# AUDIO_FM_LC_00.net
KiCad netlist of a schematic drawn in Altium Designer
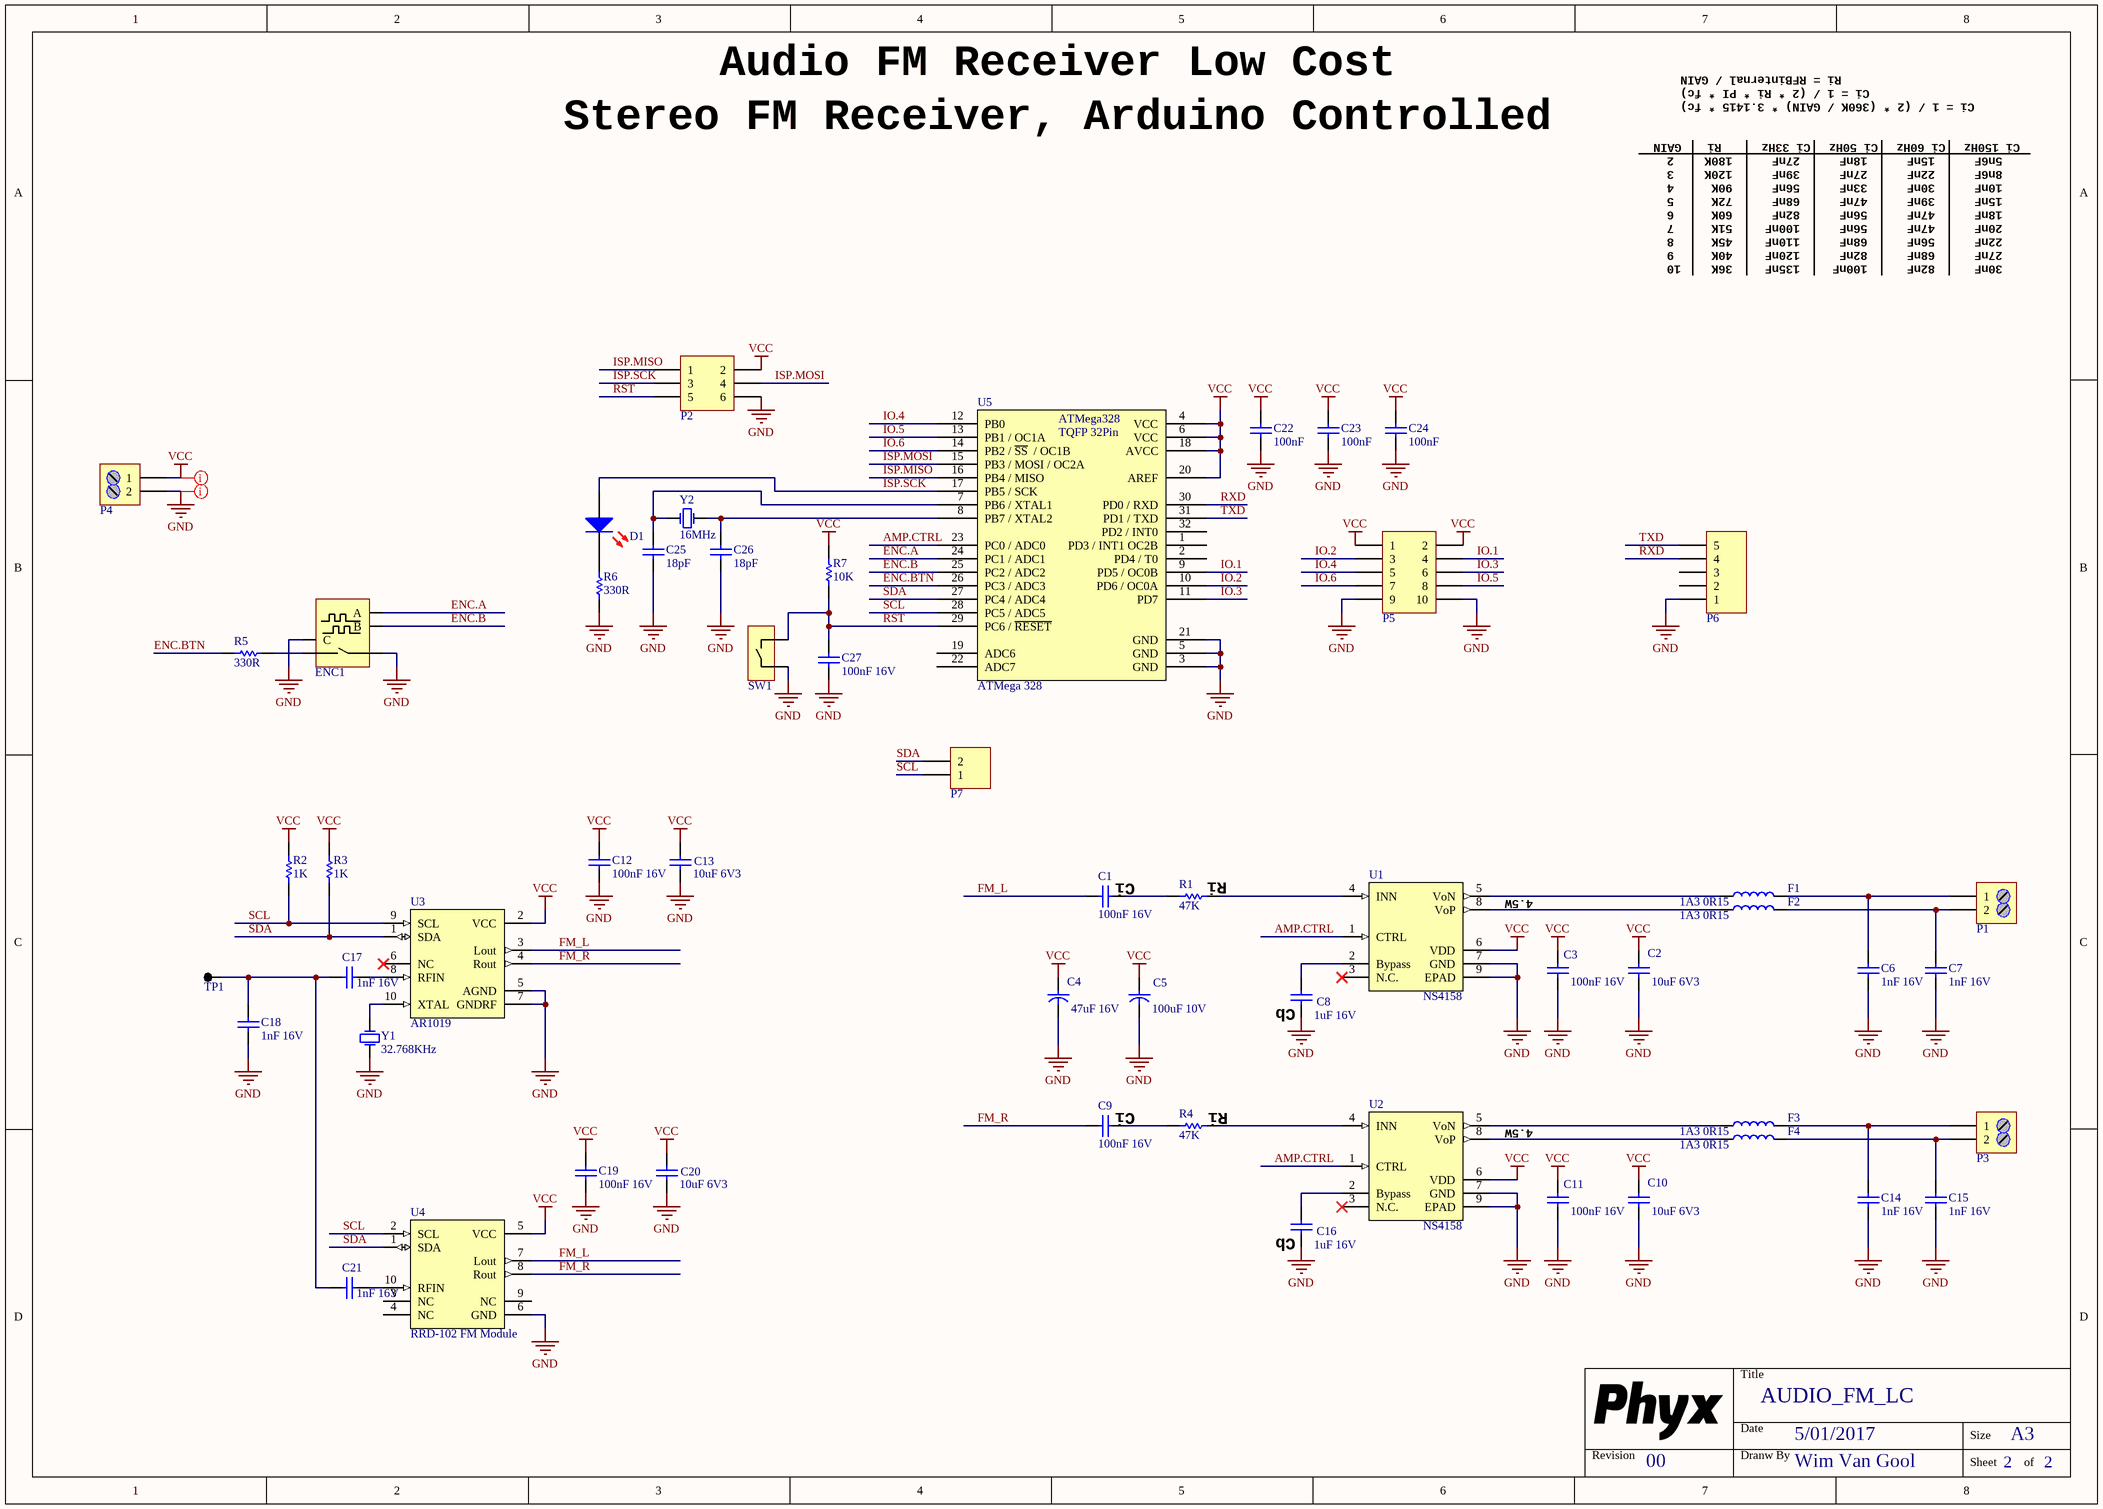
[diagram p0: AUDIO_FM_LC_00.SchDoc]

(export (version "E")
  (design (tool "Eeschema 10.0.6"))
  (components
    (comp (ref "C1")
      (value "100nF 16V")
      (footprint "C0603_N")
      (description "Capacitor Ceramic")
      (fields (field (name "Comment") "CAP_CERAMIC"))
      (libsource (lib "Phyx_Components") (part "CAP_CERAMIC"))
    )
    (comp (ref "C2")
      (value "10uF 6V3")
      (footprint "C0805_N")
      (description "Capacitor Ceramic")
      (fields (field (name "Comment") "CAP_CERAMIC"))
      (libsource (lib "Phyx_Components") (part "CAP_CERAMIC"))
    )
    (comp (ref "C3")
      (value "100nF 16V")
      (footprint "C0603_N")
      (description "Capacitor Ceramic")
      (fields (field (name "Comment") "CAP_CERAMIC"))
      (libsource (lib "Phyx_Components") (part "CAP_CERAMIC"))
    )
    (comp (ref "C4")
      (value "47uF 16V")
      (footprint "C6.6x5.4")
      (description "Capacitor electrolyt")
      (fields (field (name "Comment") "CAP_POL"))
      (libsource (lib "Phyx_Components") (part "CAP_POL"))
    )
    (comp (ref "C5")
      (value "100uF 10V")
      (footprint "C_5x11_2mm")
      (description "Capacitor electrolyt")
      (fields (field (name "Comment") "CAP_POL"))
      (libsource (lib "Phyx_Components") (part "CAP_POL"))
    )
    (comp (ref "C6")
      (value "1nF 16V")
      (footprint "C0603_N")
      (description "Capacitor Ceramic")
      (fields (field (name "Comment") "CAP_CERAMIC"))
      (libsource (lib "Phyx_Components") (part "CAP_CERAMIC"))
    )
    (comp (ref "C7")
      (value "1nF 16V")
      (footprint "C0603_N")
      (description "Capacitor Ceramic")
      (fields (field (name "Comment") "CAP_CERAMIC"))
      (libsource (lib "Phyx_Components") (part "CAP_CERAMIC"))
    )
    (comp (ref "C8")
      (value "1uF 16V")
      (footprint "C0805_N")
      (description "Capacitor Ceramic")
      (fields (field (name "Comment") "CAP_CERAMIC"))
      (libsource (lib "Phyx_Components") (part "CAP_CERAMIC"))
    )
    (comp (ref "C9")
      (value "100nF 16V")
      (footprint "C0603_N")
      (description "Capacitor Ceramic")
      (fields (field (name "Comment") "CAP_CERAMIC"))
      (libsource (lib "Phyx_Components") (part "CAP_CERAMIC"))
    )
    (comp (ref "C10")
      (value "10uF 6V3")
      (footprint "C0805_N")
      (description "Capacitor Ceramic")
      (fields (field (name "Comment") "CAP_CERAMIC"))
      (libsource (lib "Phyx_Components") (part "CAP_CERAMIC"))
    )
    (comp (ref "C11")
      (value "100nF 16V")
      (footprint "C0603_N")
      (description "Capacitor Ceramic")
      (fields (field (name "Comment") "CAP_CERAMIC"))
      (libsource (lib "Phyx_Components") (part "CAP_CERAMIC"))
    )
    (comp (ref "C12")
      (value "100nF 16V")
      (footprint "C0603_N")
      (description "Capacitor Ceramic")
      (fields (field (name "Comment") "CAP_CERAMIC"))
      (libsource (lib "Phyx_Components") (part "CAP_CERAMIC"))
    )
    (comp (ref "C13")
      (value "10uF 6V3")
      (footprint "C0805_N")
      (description "Capacitor Ceramic")
      (fields (field (name "Comment") "CAP_CERAMIC"))
      (libsource (lib "Phyx_Components") (part "CAP_CERAMIC"))
    )
    (comp (ref "C14")
      (value "1nF 16V")
      (footprint "C0603_N")
      (description "Capacitor Ceramic")
      (fields (field (name "Comment") "CAP_CERAMIC"))
      (libsource (lib "Phyx_Components") (part "CAP_CERAMIC"))
    )
    (comp (ref "C15")
      (value "1nF 16V")
      (footprint "C0603_N")
      (description "Capacitor Ceramic")
      (fields (field (name "Comment") "CAP_CERAMIC"))
      (libsource (lib "Phyx_Components") (part "CAP_CERAMIC"))
    )
    (comp (ref "C16")
      (value "1uF 16V")
      (footprint "C0805_N")
      (description "Capacitor Ceramic")
      (fields (field (name "Comment") "CAP_CERAMIC"))
      (libsource (lib "Phyx_Components") (part "CAP_CERAMIC"))
    )
    (comp (ref "C17")
      (value "1nF 16V")
      (footprint "C0603_N")
      (description "Capacitor Ceramic")
      (fields (field (name "Comment") "CAP_CERAMIC"))
      (libsource (lib "Phyx_Components") (part "CAP_CERAMIC"))
    )
    (comp (ref "C18")
      (value "1nF 16V")
      (footprint "C0603_N")
      (description "Capacitor Ceramic")
      (fields (field (name "Comment") "CAP_CERAMIC"))
      (libsource (lib "Phyx_Components") (part "CAP_CERAMIC"))
    )
    (comp (ref "C19")
      (value "100nF 16V")
      (footprint "C0603_N")
      (description "Capacitor Ceramic")
      (fields (field (name "Comment") "CAP_CERAMIC"))
      (libsource (lib "Phyx_Components") (part "CAP_CERAMIC"))
    )
    (comp (ref "C20")
      (value "10uF 6V3")
      (footprint "C0805_N")
      (description "Capacitor Ceramic")
      (fields (field (name "Comment") "CAP_CERAMIC"))
      (libsource (lib "Phyx_Components") (part "CAP_CERAMIC"))
    )
    (comp (ref "C21")
      (value "1nF 16V")
      (footprint "C0603_N")
      (description "Capacitor Ceramic")
      (fields (field (name "Comment") "CAP_CERAMIC"))
      (libsource (lib "Phyx_Components") (part "CAP_CERAMIC"))
    )
    (comp (ref "C22")
      (value "100nF")
      (footprint "C0603_N")
      (description "Capacitor Ceramic")
      (fields (field (name "Comment") "CAP_CERAMIC"))
      (libsource (lib "Phyx_Components") (part "CAP_CERAMIC"))
    )
    (comp (ref "C23")
      (value "100nF")
      (footprint "C0603_N")
      (description "Capacitor Ceramic")
      (fields (field (name "Comment") "CAP_CERAMIC"))
      (libsource (lib "Phyx_Components") (part "CAP_CERAMIC"))
    )
    (comp (ref "C24")
      (value "100nF")
      (footprint "C0603_N")
      (description "Capacitor Ceramic")
      (fields (field (name "Comment") "CAP_CERAMIC"))
      (libsource (lib "Phyx_Components") (part "CAP_CERAMIC"))
    )
    (comp (ref "C25")
      (value "18pF")
      (footprint "C0603_N")
      (description "Capacitor Ceramic")
      (fields (field (name "Comment") "CAP_CERAMIC"))
      (libsource (lib "Phyx_Components") (part "CAP_CERAMIC"))
    )
    (comp (ref "C26")
      (value "18pF")
      (footprint "C0603_N")
      (description "Capacitor Ceramic")
      (fields (field (name "Comment") "CAP_CERAMIC"))
      (libsource (lib "Phyx_Components") (part "CAP_CERAMIC"))
    )
    (comp (ref "C27")
      (value "100nF 16V")
      (footprint "C0603_N")
      (description "Capacitor Ceramic")
      (fields (field (name "Comment") "CAP_CERAMIC"))
      (libsource (lib "Phyx_Components") (part "CAP_CERAMIC"))
    )
    (comp (ref "D1")
      (value "Default 0805 Red LED")
      (footprint "LED_0805_RD")
      (description "=Description")
      (libsource (lib "Phyx_Components") (part "LED_RED"))
    )
    (comp (ref "ENC1")
      (value "Rotary Encoder with Switch")
      (footprint "PEC11-4215F-S0024")
      (libsource (lib "Phyx_Components") (part "ROT_ENC_3P_SW"))
    )
    (comp (ref "F1")
      (value "1A3 0R15")
      (footprint "L0603")
      (fields (field (name "Comment") "BLM18KG601SN1D"))
      (libsource (lib "Phyx_Components") (part "FERRITE"))
    )
    (comp (ref "F2")
      (value "1A3 0R15")
      (footprint "L0603")
      (fields (field (name "Comment") "BLM18KG601SN1D"))
      (libsource (lib "Phyx_Components") (part "FERRITE"))
    )
    (comp (ref "F3")
      (value "1A3 0R15")
      (footprint "L0603")
      (fields (field (name "Comment") "BLM18KG601SN1D"))
      (libsource (lib "Phyx_Components") (part "FERRITE"))
    )
    (comp (ref "F4")
      (value "1A3 0R15")
      (footprint "L0603")
      (fields (field (name "Comment") "BLM18KG601SN1D"))
      (libsource (lib "Phyx_Components") (part "FERRITE"))
    )
    (comp (ref "P1")
      (value "2 Way Screw HDR 3,5mm")
      (footprint "WE_691103110002")
      (libsource (lib "Phyx_Components") (part "TERM_BLCK_2"))
    )
    (comp (ref "P2")
      (value "Header 3X2")
      (footprint "HDR2X3")
      (libsource (lib "Phyx_Components") (part "Header 3X2"))
    )
    (comp (ref "P3")
      (value "2 Way Screw HDR 3,5mm")
      (footprint "WE_691103110002")
      (libsource (lib "Phyx_Components") (part "TERM_BLCK_2"))
    )
    (comp (ref "P4")
      (value "2 Way Screw HDR 3,5mm")
      (footprint "WE_691103110002")
      (libsource (lib "") (part "TERM_BLCK_2_1"))
    )
    (comp (ref "P5")
      (value "Header 5x2")
      (footprint "HDR2X5")
      (libsource (lib "Phyx_Components") (part "Header 5X2"))
    )
    (comp (ref "P6")
      (value "Header 5")
      (footprint "HDR1X5")
      (libsource (lib "Phyx_Components") (part "Header 5"))
    )
    (comp (ref "P7")
      (value "Header 2")
      (footprint "HDR1X2")
      (description "Pin Header 2.54mm 2way")
      (libsource (lib "Phyx_Components") (part "Header 2"))
    )
    (comp (ref "R1")
      (value "47K")
      (footprint "R0603_N")
      (fields (field (name "Comment") "RESISTOR"))
      (libsource (lib "Phyx_Components") (part "RESISTOR"))
    )
    (comp (ref "R2")
      (value "1K")
      (footprint "R0603_N")
      (fields (field (name "Comment") "RESISTOR"))
      (libsource (lib "Phyx_Components") (part "RESISTOR"))
    )
    (comp (ref "R3")
      (value "1K")
      (footprint "R0603_N")
      (fields (field (name "Comment") "RESISTOR"))
      (libsource (lib "Phyx_Components") (part "RESISTOR"))
    )
    (comp (ref "R4")
      (value "47K")
      (footprint "R0603_N")
      (fields (field (name "Comment") "RESISTOR"))
      (libsource (lib "Phyx_Components") (part "RESISTOR"))
    )
    (comp (ref "R5")
      (value "330R")
      (footprint "R0603_N")
      (fields (field (name "Comment") "RESISTOR"))
      (libsource (lib "Phyx_Components") (part "RESISTOR"))
    )
    (comp (ref "R6")
      (value "330R")
      (footprint "R0603_N")
      (fields (field (name "Comment") "RESISTOR"))
      (libsource (lib "Phyx_Components") (part "RESISTOR"))
    )
    (comp (ref "R7")
      (value "10K")
      (footprint "R0603_N")
      (fields (field (name "Comment") "RESISTOR"))
      (libsource (lib "Phyx_Components") (part "RESISTOR"))
    )
    (comp (ref "SW1")
      (value "Default TH TACT")
      (footprint "TACTSW")
      (description "SW TACT")
      (libsource (lib "Phyx_Components") (part "SW_TACT"))
    )
    (comp (ref "TP1")
      (value "TEST_PAD")
      (footprint "TP_1.5mm_0.9mm")
      (libsource (lib "Phyx_Components") (part "TEST_PAD"))
    )
    (comp (ref "U1")
      (value "NS4158")
      (footprint "SOIC_N_8_TH")
      (description "=Description")
      (fields (field (name "Comment") "5W Class D mono amplifier inducter-less"))
      (libsource (lib "Phyx_Components") (part "NS4158"))
    )
    (comp (ref "U2")
      (value "NS4158")
      (footprint "SOIC_N_8_TH")
      (description "=Description")
      (fields (field (name "Comment") "5W Class D mono amplifier inducter-less"))
      (libsource (lib "Phyx_Components") (part "NS4158"))
    )
    (comp (ref "U3")
      (value "AR1019")
      (footprint "TI_DGS_S-PDSO-G10")
      (description "=Description")
      (fields (field (name "Comment") "FM Receiver I2C"))
      (libsource (lib "Phyx_Components") (part "AR1019"))
    )
    (comp (ref "U4")
      (value "RRD-102 FM Module")
      (footprint "RRD-102")
      (description "=Description")
      (fields (field (name "Comment") "RRD-102 V2.0 FM Radio Module With RDS decoding"))
      (libsource (lib "Phyx_Components") (part "RRD-102"))
    )
    (comp (ref "U5")
      (value "ATMega 328")
      (footprint "TQFP_32")
      (description "ATMega328 SMD TQFP")
      (fields (field (name "Comment") "8-bit MCU"))
      (libsource (lib "Phyx_Components") (part "ATMega328_TQFP32"))
    )
    (comp (ref "Y1")
      (value "32.768KHz")
      (footprint "CMR200T")
      (description "Crystal Oscillator")
      (fields (field (name "Comment") "32.768Khz CMR200 12.5pF"))
      (libsource (lib "Phyx_Components") (part "XTAL"))
    )
    (comp (ref "Y2")
      (value "16MHz")
      (footprint "HC49US")
      (description "Crystal Oscillator")
      (fields (field (name "Comment") "16MHz 18pF HC49US"))
      (libsource (lib "Phyx_Components") (part "XTAL"))
    )
  )
  (nets
    (net (code "1") (name "/AMP.CTRL") (class "Default")
      (node (ref "U1") (pin "1") (pinfunction "CTRL_1") (pintype "input"))
      (node (ref "U2") (pin "1") (pinfunction "CTRL_1") (pintype "input"))
      (node (ref "U5") (pin "23") (pinfunction "PC0_/_ADC0_23") (pintype "passive"))
    )
    (net (code "2") (name "/ENC.A") (class "Default")
      (node (ref "ENC1") (pin "A") (pinfunction "A_A") (pintype "passive"))
      (node (ref "U5") (pin "24") (pinfunction "PC1_/_ADC1_24") (pintype "passive"))
    )
    (net (code "3") (name "/ENC.B") (class "Default")
      (node (ref "ENC1") (pin "B") (pinfunction "B_B") (pintype "passive"))
      (node (ref "U5") (pin "25") (pinfunction "PC2_/_ADC2_25") (pintype "passive"))
    )
    (net (code "4") (name "/ENC.BTN") (class "Default")
      (node (ref "R5") (pin "1") (pinfunction "1_1") (pintype "passive"))
      (node (ref "U5") (pin "26") (pinfunction "PC3_/_ADC3_26") (pintype "passive"))
    )
    (net (code "5") (name "/FM_L") (class "Default")
      (node (ref "C1") (pin "1") (pinfunction "1_1") (pintype "passive"))
      (node (ref "U3") (pin "3") (pinfunction "Lout_3") (pintype "output"))
      (node (ref "U4") (pin "7") (pinfunction "Lout_7") (pintype "output"))
    )
    (net (code "6") (name "/FM_R") (class "Default")
      (node (ref "C9") (pin "1") (pinfunction "1_1") (pintype "passive"))
      (node (ref "U3") (pin "4") (pinfunction "Rout_4") (pintype "output"))
      (node (ref "U4") (pin "8") (pinfunction "Rout_8") (pintype "output"))
    )
    (net (code "7") (name "/IO.1") (class "Default")
      (node (ref "P5") (pin "4") (pinfunction "4_4") (pintype "passive"))
      (node (ref "U5") (pin "9") (pinfunction "PD5_/_OC0B_9") (pintype "passive"))
    )
    (net (code "8") (name "/IO.2") (class "Default")
      (node (ref "P5") (pin "3") (pinfunction "3_3") (pintype "passive"))
      (node (ref "U5") (pin "10") (pinfunction "PD6_/_OC0A_10") (pintype "passive"))
    )
    (net (code "9") (name "/IO.3") (class "Default")
      (node (ref "P5") (pin "6") (pinfunction "6_6") (pintype "passive"))
      (node (ref "U5") (pin "11") (pinfunction "PD7_11") (pintype "passive"))
    )
    (net (code "10") (name "/IO.4") (class "Default")
      (node (ref "P5") (pin "5") (pinfunction "5_5") (pintype "passive"))
      (node (ref "U5") (pin "12") (pinfunction "PB0_12") (pintype "passive"))
    )
    (net (code "11") (name "/IO.5") (class "Default")
      (node (ref "P5") (pin "8") (pinfunction "8_8") (pintype "passive"))
      (node (ref "U5") (pin "13") (pinfunction "PB1_/_OC1A_13") (pintype "passive"))
    )
    (net (code "12") (name "/IO.6") (class "Default")
      (node (ref "P5") (pin "7") (pinfunction "7_7") (pintype "passive"))
      (node (ref "U5") (pin "14") (pinfunction "PB2_/_~{SS}__/_OC1B_14") (pintype "passive"))
    )
    (net (code "13") (name "/ISP.MISO") (class "Default")
      (node (ref "P2") (pin "1") (pinfunction "1_1") (pintype "passive"))
      (node (ref "U5") (pin "16") (pinfunction "PB4_/_MISO_16") (pintype "passive"))
    )
    (net (code "14") (name "/ISP.MOSI") (class "Default")
      (node (ref "P2") (pin "4") (pinfunction "4_4") (pintype "passive"))
      (node (ref "U5") (pin "15") (pinfunction "PB3_/_MOSI_/_OC2A_15") (pintype "passive"))
    )
    (net (code "15") (name "/ISP.SCK") (class "Default")
      (node (ref "D1") (pin "1") (pinfunction "A_1") (pintype "passive"))
      (node (ref "P2") (pin "3") (pinfunction "3_3") (pintype "passive"))
      (node (ref "U5") (pin "17") (pinfunction "PB5_/_SCK_17") (pintype "passive"))
    )
    (net (code "16") (name "/RST") (class "Default")
      (node (ref "C27") (pin "1") (pinfunction "1_1") (pintype "passive"))
      (node (ref "P2") (pin "5") (pinfunction "5_5") (pintype "passive"))
      (node (ref "R7") (pin "2") (pinfunction "2_2") (pintype "passive"))
      (node (ref "SW1") (pin "1") (pinfunction "1_1") (pintype "passive"))
      (node (ref "U5") (pin "29") (pinfunction "PC6_/_~{RESET}_29") (pintype "passive"))
    )
    (net (code "17") (name "/RXD") (class "Default")
      (node (ref "P6") (pin "4") (pinfunction "4_4") (pintype "passive"))
      (node (ref "U5") (pin "30") (pinfunction "PD0_/_RXD_30") (pintype "passive"))
    )
    (net (code "18") (name "/SCL") (class "Default")
      (node (ref "P7") (pin "1") (pinfunction "1_1") (pintype "passive"))
      (node (ref "R2") (pin "2") (pinfunction "2_2") (pintype "passive"))
      (node (ref "U3") (pin "9") (pinfunction "SCL_9") (pintype "input"))
      (node (ref "U4") (pin "2") (pinfunction "SCL_2") (pintype "input"))
      (node (ref "U5") (pin "28") (pinfunction "PC5_/_ADC5_28") (pintype "passive"))
    )
    (net (code "19") (name "/SDA") (class "Default")
      (node (ref "P7") (pin "2") (pinfunction "2_2") (pintype "passive"))
      (node (ref "R3") (pin "2") (pinfunction "2_2") (pintype "passive"))
      (node (ref "U3") (pin "1") (pinfunction "SDA_1") (pintype "bidirectional"))
      (node (ref "U4") (pin "1") (pinfunction "SDA_1") (pintype "bidirectional"))
      (node (ref "U5") (pin "27") (pinfunction "PC4_/_ADC4_27") (pintype "passive"))
    )
    (net (code "20") (name "/TXD") (class "Default")
      (node (ref "P6") (pin "5") (pinfunction "5_5") (pintype "passive"))
      (node (ref "U5") (pin "31") (pinfunction "PD1_/_TXD_31") (pintype "passive"))
    )
    (net (code "21") (name "GND") (class "Default")
      (node (ref "C10") (pin "2") (pinfunction "2_2") (pintype "passive"))
      (node (ref "C11") (pin "2") (pinfunction "2_2") (pintype "passive"))
      (node (ref "C12") (pin "2") (pinfunction "2_2") (pintype "passive"))
      (node (ref "C13") (pin "2") (pinfunction "2_2") (pintype "passive"))
      (node (ref "C14") (pin "2") (pinfunction "2_2") (pintype "passive"))
      (node (ref "C15") (pin "2") (pinfunction "2_2") (pintype "passive"))
      (node (ref "C16") (pin "2") (pinfunction "2_2") (pintype "passive"))
      (node (ref "C18") (pin "2") (pinfunction "2_2") (pintype "passive"))
      (node (ref "C19") (pin "2") (pinfunction "2_2") (pintype "passive"))
      (node (ref "C2") (pin "2") (pinfunction "2_2") (pintype "passive"))
      (node (ref "C20") (pin "2") (pinfunction "2_2") (pintype "passive"))
      (node (ref "C22") (pin "2") (pinfunction "2_2") (pintype "passive"))
      (node (ref "C23") (pin "2") (pinfunction "2_2") (pintype "passive"))
      (node (ref "C24") (pin "2") (pinfunction "2_2") (pintype "passive"))
      (node (ref "C25") (pin "2") (pinfunction "2_2") (pintype "passive"))
      (node (ref "C26") (pin "2") (pinfunction "2_2") (pintype "passive"))
      (node (ref "C27") (pin "2") (pinfunction "2_2") (pintype "passive"))
      (node (ref "C3") (pin "2") (pinfunction "2_2") (pintype "passive"))
      (node (ref "C4") (pin "2") (pinfunction "2_2") (pintype "passive"))
      (node (ref "C5") (pin "2") (pinfunction "2_2") (pintype "passive"))
      (node (ref "C6") (pin "2") (pinfunction "2_2") (pintype "passive"))
      (node (ref "C7") (pin "2") (pinfunction "2_2") (pintype "passive"))
      (node (ref "C8") (pin "2") (pinfunction "2_2") (pintype "passive"))
      (node (ref "ENC1") (pin "2") (pinfunction "2_2") (pintype "passive"))
      (node (ref "ENC1") (pin "C") (pinfunction "C_C") (pintype "passive"))
      (node (ref "P2") (pin "6") (pinfunction "6_6") (pintype "passive"))
      (node (ref "P4") (pin "2") (pinfunction "2_2") (pintype "passive"))
      (node (ref "P5") (pin "10") (pinfunction "10_10") (pintype "passive"))
      (node (ref "P5") (pin "9") (pinfunction "9_9") (pintype "passive"))
      (node (ref "P6") (pin "1") (pinfunction "1_1") (pintype "passive"))
      (node (ref "R6") (pin "2") (pinfunction "2_2") (pintype "passive"))
      (node (ref "SW1") (pin "2") (pinfunction "2_2") (pintype "passive"))
      (node (ref "U1") (pin "7") (pinfunction "GND_7") (pintype "power_in"))
      (node (ref "U1") (pin "9") (pinfunction "EPAD_9") (pintype "power_in"))
      (node (ref "U2") (pin "7") (pinfunction "GND_7") (pintype "power_in"))
      (node (ref "U2") (pin "9") (pinfunction "EPAD_9") (pintype "power_in"))
      (node (ref "U3") (pin "5") (pinfunction "AGND_5") (pintype "power_in"))
      (node (ref "U3") (pin "7") (pinfunction "GNDRF_7") (pintype "power_in"))
      (node (ref "U4") (pin "6") (pinfunction "GND_6") (pintype "power_in"))
      (node (ref "U5") (pin "21") (pinfunction "GND_21") (pintype "passive"))
      (node (ref "U5") (pin "3") (pinfunction "GND_3") (pintype "passive"))
      (node (ref "U5") (pin "5") (pinfunction "GND_5") (pintype "passive"))
      (node (ref "Y1") (pin "2") (pinfunction "OSC2_2") (pintype "passive"))
    )
    (net (code "22") (name "Net-(C1-Pad2)") (class "Default")
      (node (ref "C1") (pin "2") (pinfunction "2_2") (pintype "passive"))
      (node (ref "R1") (pin "2") (pinfunction "2_2") (pintype "passive"))
    )
    (net (code "23") (name "Net-(C6-Pad1)") (class "Default")
      (node (ref "C6") (pin "1") (pinfunction "1_1") (pintype "passive"))
      (node (ref "F1") (pin "2") (pinfunction "2_2") (pintype "passive"))
      (node (ref "P1") (pin "1") (pinfunction "1_1") (pintype "passive"))
    )
    (net (code "24") (name "Net-(C7-Pad1)") (class "Default")
      (node (ref "C7") (pin "1") (pinfunction "1_1") (pintype "passive"))
      (node (ref "F2") (pin "2") (pinfunction "2_2") (pintype "passive"))
      (node (ref "P1") (pin "2") (pinfunction "2_2") (pintype "passive"))
    )
    (net (code "25") (name "Net-(C9-Pad2)") (class "Default")
      (node (ref "C9") (pin "2") (pinfunction "2_2") (pintype "passive"))
      (node (ref "R4") (pin "2") (pinfunction "2_2") (pintype "passive"))
    )
    (net (code "26") (name "Net-(C14-Pad1)") (class "Default")
      (node (ref "C14") (pin "1") (pinfunction "1_1") (pintype "passive"))
      (node (ref "F3") (pin "2") (pinfunction "2_2") (pintype "passive"))
      (node (ref "P3") (pin "1") (pinfunction "1_1") (pintype "passive"))
    )
    (net (code "27") (name "Net-(C15-Pad1)") (class "Default")
      (node (ref "C15") (pin "1") (pinfunction "1_1") (pintype "passive"))
      (node (ref "F4") (pin "2") (pinfunction "2_2") (pintype "passive"))
      (node (ref "P3") (pin "2") (pinfunction "2_2") (pintype "passive"))
    )
    (net (code "28") (name "Net-(C17-Pad2)") (class "Default")
      (node (ref "C17") (pin "2") (pinfunction "2_2") (pintype "passive"))
      (node (ref "C18") (pin "1") (pinfunction "1_1") (pintype "passive"))
      (node (ref "C21") (pin "2") (pinfunction "2_2") (pintype "passive"))
      (node (ref "TP1") (pin "1") (pinfunction "1_1") (pintype "passive"))
    )
    (net (code "29") (name "Net-(D1-K)") (class "Default")
      (node (ref "D1") (pin "2") (pinfunction "K_2") (pintype "passive"))
      (node (ref "R6") (pin "1") (pinfunction "1_1") (pintype "passive"))
    )
    (net (code "30") (name "Net-(ENC1-Pad1)") (class "Default")
      (node (ref "ENC1") (pin "1") (pinfunction "1_1") (pintype "passive"))
      (node (ref "R5") (pin "2") (pinfunction "2_2") (pintype "passive"))
    )
    (net (code "31") (name "Net-(U1-Bypass)") (class "Default")
      (node (ref "C8") (pin "1") (pinfunction "1_1") (pintype "passive"))
      (node (ref "U1") (pin "2") (pinfunction "Bypass_2") (pintype "passive"))
    )
    (net (code "32") (name "Net-(U1-INN)") (class "Default")
      (node (ref "R1") (pin "1") (pinfunction "1_1") (pintype "passive"))
      (node (ref "U1") (pin "4") (pinfunction "INN_4") (pintype "input"))
    )
    (net (code "33") (name "Net-(U1-VoN)") (class "Default")
      (node (ref "F1") (pin "1") (pinfunction "1_1") (pintype "passive"))
      (node (ref "U1") (pin "5") (pinfunction "VoN_5") (pintype "output"))
    )
    (net (code "34") (name "Net-(U1-VoP)") (class "Default")
      (node (ref "F2") (pin "1") (pinfunction "1_1") (pintype "passive"))
      (node (ref "U1") (pin "8") (pinfunction "VoP_8") (pintype "output"))
    )
    (net (code "35") (name "Net-(U2-Bypass)") (class "Default")
      (node (ref "C16") (pin "1") (pinfunction "1_1") (pintype "passive"))
      (node (ref "U2") (pin "2") (pinfunction "Bypass_2") (pintype "passive"))
    )
    (net (code "36") (name "Net-(U2-INN)") (class "Default")
      (node (ref "R4") (pin "1") (pinfunction "1_1") (pintype "passive"))
      (node (ref "U2") (pin "4") (pinfunction "INN_4") (pintype "input"))
    )
    (net (code "37") (name "Net-(U2-VoN)") (class "Default")
      (node (ref "F3") (pin "1") (pinfunction "1_1") (pintype "passive"))
      (node (ref "U2") (pin "5") (pinfunction "VoN_5") (pintype "output"))
    )
    (net (code "38") (name "Net-(U2-VoP)") (class "Default")
      (node (ref "F4") (pin "1") (pinfunction "1_1") (pintype "passive"))
      (node (ref "U2") (pin "8") (pinfunction "VoP_8") (pintype "output"))
    )
    (net (code "39") (name "Net-(U3-RFIN)") (class "Default")
      (node (ref "C17") (pin "1") (pinfunction "1_1") (pintype "passive"))
      (node (ref "U3") (pin "8") (pinfunction "RFIN_8") (pintype "input"))
    )
    (net (code "40") (name "Net-(U3-XTAL)") (class "Default")
      (node (ref "U3") (pin "10") (pinfunction "XTAL_10") (pintype "input"))
      (node (ref "Y1") (pin "1") (pinfunction "OSC1_1") (pintype "passive"))
    )
    (net (code "41") (name "Net-(U4-RFIN)") (class "Default")
      (node (ref "C21") (pin "1") (pinfunction "1_1") (pintype "passive"))
      (node (ref "U4") (pin "10") (pinfunction "RFIN_10") (pintype "input"))
    )
    (net (code "42") (name "Net-(U5-PB6_{slash}_XTAL1)") (class "Default")
      (node (ref "C25") (pin "1") (pinfunction "1_1") (pintype "passive"))
      (node (ref "U5") (pin "7") (pinfunction "PB6_/_XTAL1_7") (pintype "passive"))
      (node (ref "Y2") (pin "1") (pinfunction "OSC1_1") (pintype "passive"))
    )
    (net (code "43") (name "Net-(U5-PB7_{slash}_XTAL2)") (class "Default")
      (node (ref "C26") (pin "1") (pinfunction "1_1") (pintype "passive"))
      (node (ref "U5") (pin "8") (pinfunction "PB7_/_XTAL2_8") (pintype "passive"))
      (node (ref "Y2") (pin "2") (pinfunction "OSC2_2") (pintype "passive"))
    )
    (net (code "44") (name "VCC") (class "Default")
      (node (ref "C10") (pin "1") (pinfunction "1_1") (pintype "passive"))
      (node (ref "C11") (pin "1") (pinfunction "1_1") (pintype "passive"))
      (node (ref "C12") (pin "1") (pinfunction "1_1") (pintype "passive"))
      (node (ref "C13") (pin "1") (pinfunction "1_1") (pintype "passive"))
      (node (ref "C19") (pin "1") (pinfunction "1_1") (pintype "passive"))
      (node (ref "C2") (pin "1") (pinfunction "1_1") (pintype "passive"))
      (node (ref "C20") (pin "1") (pinfunction "1_1") (pintype "passive"))
      (node (ref "C22") (pin "1") (pinfunction "1_1") (pintype "passive"))
      (node (ref "C23") (pin "1") (pinfunction "1_1") (pintype "passive"))
      (node (ref "C24") (pin "1") (pinfunction "1_1") (pintype "passive"))
      (node (ref "C3") (pin "1") (pinfunction "1_1") (pintype "passive"))
      (node (ref "C4") (pin "1") (pinfunction "1_1") (pintype "passive"))
      (node (ref "C5") (pin "1") (pinfunction "1_1") (pintype "passive"))
      (node (ref "P2") (pin "2") (pinfunction "2_2") (pintype "passive"))
      (node (ref "P4") (pin "1") (pinfunction "1_1") (pintype "passive"))
      (node (ref "P5") (pin "1") (pinfunction "1_1") (pintype "passive"))
      (node (ref "P5") (pin "2") (pinfunction "2_2") (pintype "passive"))
      (node (ref "R2") (pin "1") (pinfunction "1_1") (pintype "passive"))
      (node (ref "R3") (pin "1") (pinfunction "1_1") (pintype "passive"))
      (node (ref "R7") (pin "1") (pinfunction "1_1") (pintype "passive"))
      (node (ref "U1") (pin "6") (pinfunction "VDD_6") (pintype "power_in"))
      (node (ref "U2") (pin "6") (pinfunction "VDD_6") (pintype "power_in"))
      (node (ref "U3") (pin "2") (pinfunction "VCC_2") (pintype "power_in"))
      (node (ref "U4") (pin "5") (pinfunction "VCC_5") (pintype "power_in"))
      (node (ref "U5") (pin "18") (pinfunction "AVCC_18") (pintype "passive"))
      (node (ref "U5") (pin "20") (pinfunction "AREF_20") (pintype "passive"))
      (node (ref "U5") (pin "4") (pinfunction "VCC_4") (pintype "passive"))
      (node (ref "U5") (pin "6") (pinfunction "VCC_6") (pintype "passive"))
    )
    (net (code "45") (name "unconnected-(P6-Pad2)") (class "Default")
      (node (ref "P6") (pin "2") (pinfunction "2_2") (pintype "passive"))
    )
    (net (code "46") (name "unconnected-(P6-Pad3)") (class "Default")
      (node (ref "P6") (pin "3") (pinfunction "3_3") (pintype "passive"))
    )
    (net (code "47") (name "unconnected-(U1-N.C.-Pad3)") (class "Default")
      (node (ref "U1") (pin "3") (pinfunction "N.C._3") (pintype "passive+no_connect"))
    )
    (net (code "48") (name "unconnected-(U2-N.C.-Pad3)") (class "Default")
      (node (ref "U2") (pin "3") (pinfunction "N.C._3") (pintype "passive+no_connect"))
    )
    (net (code "49") (name "unconnected-(U3-NC-Pad6)") (class "Default")
      (node (ref "U3") (pin "6") (pinfunction "NC_6") (pintype "passive+no_connect"))
    )
    (net (code "50") (name "unconnected-(U4-NC-Pad3)") (class "Default")
      (node (ref "U4") (pin "3") (pinfunction "NC_3") (pintype "passive"))
    )
    (net (code "51") (name "unconnected-(U4-NC-Pad4)") (class "Default")
      (node (ref "U4") (pin "4") (pinfunction "NC_4") (pintype "passive"))
    )
    (net (code "52") (name "unconnected-(U4-NC-Pad9)") (class "Default")
      (node (ref "U4") (pin "9") (pinfunction "NC_9") (pintype "passive"))
    )
    (net (code "53") (name "unconnected-(U5-ADC6-Pad19)") (class "Default")
      (node (ref "U5") (pin "19") (pinfunction "ADC6_19") (pintype "passive"))
    )
    (net (code "54") (name "unconnected-(U5-ADC7-Pad22)") (class "Default")
      (node (ref "U5") (pin "22") (pinfunction "ADC7_22") (pintype "passive"))
    )
    (net (code "55") (name "unconnected-(U5-PD2_{slash}_INT0-Pad32)") (class "Default")
      (node (ref "U5") (pin "32") (pinfunction "PD2_/_INT0_32") (pintype "passive"))
    )
    (net (code "56") (name "unconnected-(U5-PD3_{slash}_INT1_OC2B-Pad1)") (class "Default")
      (node (ref "U5") (pin "1") (pinfunction "PD3_/_INT1_OC2B_1") (pintype "passive"))
    )
    (net (code "57") (name "unconnected-(U5-PD4_{slash}_T0-Pad2)") (class "Default")
      (node (ref "U5") (pin "2") (pinfunction "PD4_/_T0_2") (pintype "passive"))
    )
  )
)
